# Power_Supply.net
KiCad netlist of a schematic drawn in Altium Designer
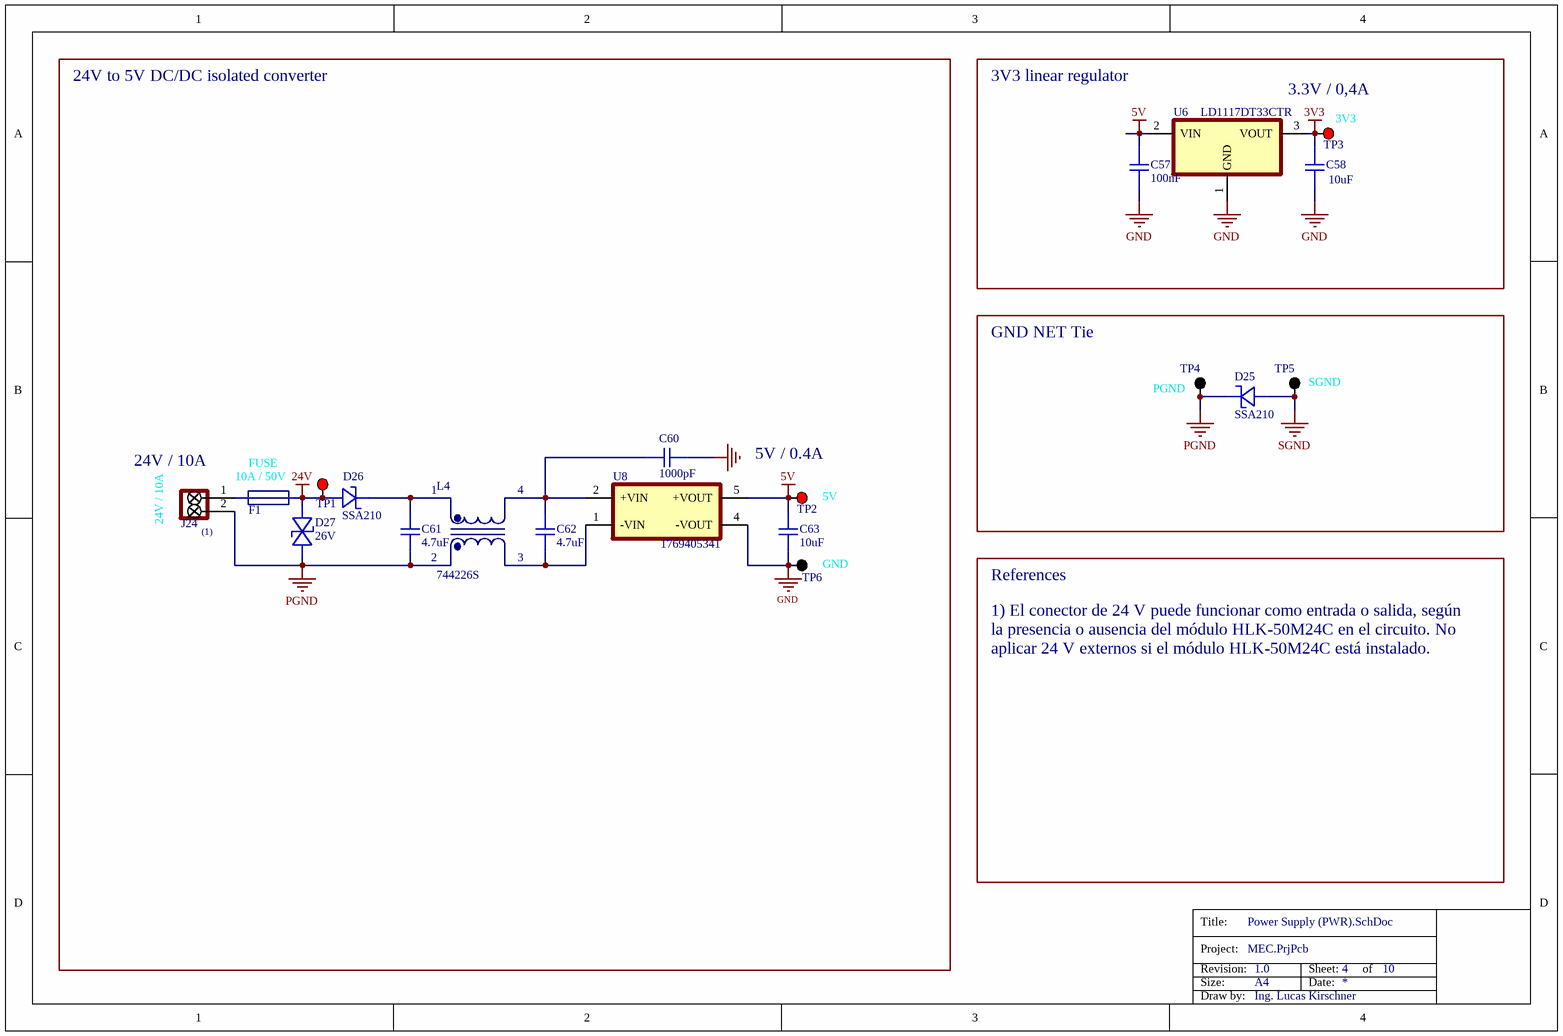
[diagram p0: Power Supply (PWR).SchDoc]

(export (version "E")
  (design (tool "Eeschema 10.0.6"))
  (components
    (comp (ref "C57")
      (value "100nF")
      (footprint "CAPC1005N")
      (description "Multilayer Ceramic Capacitors MLCC - SMD/SMT 50 V 0.1uF X7R 0402 10%")
      (fields (field (name "PART NUMBER") "CC0402KRX5R9BB104") (field (name "MANUFACTURER") "YAGEO"))
      (libsource (lib "SchLib") (part "C-MLCC-100nF-50V-10%-0402"))
    )
    (comp (ref "C58")
      (value "10uF")
      (footprint "CAPC2012N")
      (description "Multilayer Ceramic Capacitors MLCC - SMD/SMT 16V 10uF X5R 0805 10%")
      (fields (field (name "PART NUMBER") "CC0805KKX5R7BB106") (field (name "MANUFACTURER") "YAGEO"))
      (libsource (lib "SchLib") (part "C-MLCC-10uF-16V-10%-0805"))
    )
    (comp (ref "C60")
      (value "1000pF")
      (footprint "CAPC3216N")
      (description "Multilayer Ceramic Capacitors MLCC - SMD/SMT 2kV 1000pF X7R 1206 10%")
      (fields (field (name "PART NUMBER") "CC1206KKX7RDBB102") (field (name "MANUFACTURER") "YAGEO"))
      (libsource (lib "SchLib") (part "C-MLCC-1000pF-2kV-10%-1206"))
    )
    (comp (ref "C61")
      (value "4.7uF")
      (footprint "CAPC2012N")
      (description "Multilayer Ceramic Capacitors MLCC - SMD/SMT 50V 4.7uF X5R 0805 10%")
      (fields (field (name "PART NUMBER") "CC0805KKX5R9BB475") (field (name "MANUFACTURER") "YAGEO"))
      (libsource (lib "SchLib") (part "C-MLCC-4.7uF-50V-10%-0805"))
    )
    (comp (ref "C62")
      (value "4.7uF")
      (footprint "CAPC2012N")
      (description "Multilayer Ceramic Capacitors MLCC - SMD/SMT 50V 4.7uF X5R 0805 10%")
      (fields (field (name "PART NUMBER") "CC0805KKX5R9BB475") (field (name "MANUFACTURER") "YAGEO"))
      (libsource (lib "SchLib") (part "C-MLCC-4.7uF-50V-10%-0805"))
    )
    (comp (ref "C63")
      (value "10uF")
      (footprint "CAPC2012N")
      (description "Multilayer Ceramic Capacitors MLCC - SMD/SMT 16V 10uF X5R 0805 10%")
      (fields (field (name "PART NUMBER") "CC0805KKX5R7BB106") (field (name "MANUFACTURER") "YAGEO"))
      (libsource (lib "SchLib") (part "C-MLCC-10uF-16V-10%-0805"))
    )
    (comp (ref "D25")
      (value "Schottky Diodes")
      (footprint "DIOM5026X229N")
      (description "Schottky Diodes & Rectifiers 2A 100V SMA")
      (fields
        (field (name "MANUFACTURER") "onsemi")
        (field (name "MOUSER PART #") "512-SSA210")
        (field (name "PART NUMBER") "SSA210")
      )
      (libsource (lib "SchLib") (part "D-SCH-2A-100V-SMA"))
    )
    (comp (ref "D26")
      (value "Schottky Diodes")
      (footprint "DIOM5026X229N")
      (description "Schottky Diodes & Rectifiers 2A 100V SMA")
      (fields
        (field (name "MANUFACTURER") "onsemi")
        (field (name "MOUSER PART #") "512-SSA210")
        (field (name "PART NUMBER") "SSA210")
      )
      (libsource (lib "SchLib") (part "D-SCH-2A-100V-SMA"))
    )
    (comp (ref "D27")
      (value "26V")
      (footprint "DIOM5026X229N_NP")
      (description "ESD Protection Diodes / TVS Diodes 400W 26V 5% Bi-Directional")
      (fields (field (name "PART NUMBER") "SMAJ26CA") (field (name "MANUFACTURER") "Littelfuse"))
      (libsource (lib "SchLib") (part "D-TVS-400W-26V-SMA-BI"))
    )
    (comp (ref "F1")
      (value "Cartridge Fuse")
      (footprint "RESC3216N")
      (description "Surface Mount Fuses 1206 high-current met-foil. 10A")
      (fields (field (name "MANUFACTURER") "Bourns") (field (name "MOUSER PART #") "652-SF-1206HH1000R-2"))
      (libsource (lib "SchLib") (part "F-1206-10A-50V-SMT"))
    )
    (comp (ref "J24")
      (value "Terminal Blocks")
      (footprint "CONB_FIX508P-2N")
      (description "Pluggable Terminal Blocks 2 Pos 5.08mm pitch Through Hole Header")
      (fields (field (name "MOUSER PART #") "737-EBA-02-D-BU-01") (field (name "MANUFACTURER") "Adam Tech"))
      (libsource (lib "SchLib") (part "J-02-5P08-TERM-F-VERT-TH"))
    )
    (comp (ref "L4")
      (value "Common Mode Chokes")
      (footprint "INDC6X9.2-4N")
      (description "Common Mode Chokes / Filters WE-SL2 SMD Sectional 2x10uH 1600mA")
      (fields
        (field (name "MANUFACTURER") "Wurth Elektronik")
        (field (name "MOUSER PART #") "710-744226S")
        (field (name "PART NUMBER") "744226S")
      )
      (libsource (lib "SchLib") (part "L-CMC-10uH-1.6A-TH"))
    )
    (comp (ref "TP1")
      (value "Test point")
      (footprint "TP-1MM")
      (description "Test point, 1mm, exposed pad")
      (fields (field (name "JLCPCB PART #") "C5199810"))
      (libsource (lib "SchLib") (part "TP-1MM-SMD"))
    )
    (comp (ref "TP2")
      (value "Test point")
      (footprint "TP-1MM")
      (description "Test point, 1mm, exposed pad")
      (fields (field (name "JLCPCB PART #") "C5199810"))
      (libsource (lib "SchLib") (part "TP-1MM-SMD"))
    )
    (comp (ref "TP3")
      (value "Test point")
      (footprint "TP-1MM")
      (description "Test point, 1mm, exposed pad")
      (fields (field (name "JLCPCB PART #") "C5199810"))
      (libsource (lib "SchLib") (part "TP-1MM-SMD"))
    )
    (comp (ref "TP4")
      (value "Test point")
      (footprint "TPH1.6D3.2BLK")
      (description "Test point black, Mtg Hole 1.6, loop 3.2mm")
      (fields (field (name "PART NUMBER") "5006") (field (name "MANUFACTURER") "Keystone Electronics"))
      (libsource (lib "SchLib") (part "TP-LOOP-D3.2-P1.60-BLK-TH"))
    )
    (comp (ref "TP5")
      (value "Test point")
      (footprint "TPH1.6D3.2BLK")
      (description "Test point black, Mtg Hole 1.6, loop 3.2mm")
      (fields (field (name "PART NUMBER") "5006") (field (name "MANUFACTURER") "Keystone Electronics"))
      (libsource (lib "SchLib") (part "TP-LOOP-D3.2-P1.60-BLK-TH"))
    )
    (comp (ref "TP6")
      (value "Test point")
      (footprint "TPH1.6D3.2BLK")
      (description "Test point black, Mtg Hole 1.6, loop 3.2mm")
      (fields (field (name "PART NUMBER") "5006") (field (name "MANUFACTURER") "Keystone Electronics"))
      (libsource (lib "SchLib") (part "TP-LOOP-D3.2-P1.60-BLK-TH"))
    )
    (comp (ref "U6")
      (value "LDO Voltage Regulators")
      (footprint "TO252P170-3N")
      (description "LDO Voltage Regulators 3.3V 0.8A Positive")
      (fields
        (field (name "MANUFACTURER") "STMicroelectronics")
        (field (name "MOUSER PART #") "511-LD1117DT33C-TR")
        (field (name "PART NUMBER") "LD1117DT33CTR")
      )
      (libsource (lib "SchLib") (part "U-LD1117DT33CTR"))
    )
    (comp (ref "U8")
      (value "Isolated DC/DC Converter")
      (footprint "PKG10.8X12.8-5N")
      (description "Isolated DC/DC Converters - SMD WPME-FISM SMT-8 Modu 24Vin 5Vout 2W 3kV")
      (fields
        (field (name "MANUFACTURER") "Wurth Elektronik")
        (field (name "MOUSER PART #") "710-1769405341")
        (field (name "PART NUMBER") "1769405341")
      )
      (libsource (lib "SchLib") (part "U-1769405341-SMD"))
    )
  )
  (nets
    (net (code "1") (name "3V3") (class "Default")
      (node (ref "C58") (pin "1") (pinfunction "1_1") (pintype "passive"))
      (node (ref "TP3") (pin "1") (pinfunction "1_1") (pintype "passive"))
      (node (ref "U6") (pin "3") (pinfunction "VOUT_3") (pintype "passive"))
    )
    (net (code "2") (name "5V") (class "Default")
      (node (ref "C57") (pin "1") (pinfunction "1_1") (pintype "passive"))
      (node (ref "C63") (pin "1") (pinfunction "1_1") (pintype "passive"))
      (node (ref "TP2") (pin "1") (pinfunction "1_1") (pintype "passive"))
      (node (ref "U6") (pin "2") (pinfunction "VIN_2") (pintype "passive"))
      (node (ref "U8") (pin "5") (pinfunction "+VOUT_5") (pintype "passive"))
    )
    (net (code "3") (name "24V") (class "Default")
      (node (ref "D26") (pin "A") (pinfunction "A_A") (pintype "passive"))
      (node (ref "D27") (pin "2") (pinfunction "2_2") (pintype "passive"))
      (node (ref "F1") (pin "2") (pinfunction "2_2") (pintype "passive"))
      (node (ref "TP1") (pin "1") (pinfunction "1_1") (pintype "passive"))
    )
    (net (code "4") (name "GND") (class "Default")
      (node (ref "C57") (pin "2") (pinfunction "2_2") (pintype "passive"))
      (node (ref "C58") (pin "2") (pinfunction "2_2") (pintype "passive"))
      (node (ref "C60") (pin "2") (pinfunction "2_2") (pintype "passive"))
      (node (ref "C63") (pin "2") (pinfunction "2_2") (pintype "passive"))
      (node (ref "TP6") (pin "1") (pinfunction "1_1") (pintype "passive"))
      (node (ref "U6") (pin "1") (pinfunction "GND_1") (pintype "passive"))
      (node (ref "U8") (pin "4") (pinfunction "-VOUT_4") (pintype "passive"))
    )
    (net (code "5") (name "Net-(C61-Pad1)") (class "Default")
      (node (ref "C61") (pin "1") (pinfunction "1_1") (pintype "passive"))
      (node (ref "D26") (pin "C") (pinfunction "C_C") (pintype "passive"))
      (node (ref "L4") (pin "1") (pinfunction "1_1") (pintype "passive"))
    )
    (net (code "6") (name "Net-(F1-Pad1)") (class "Default")
      (node (ref "F1") (pin "1") (pinfunction "1_1") (pintype "passive"))
      (node (ref "J24") (pin "1") (pinfunction "1_1") (pintype "passive"))
    )
    (net (code "7") (name "Net-(U8-+VIN)") (class "Default")
      (node (ref "C60") (pin "1") (pinfunction "1_1") (pintype "passive"))
      (node (ref "C62") (pin "1") (pinfunction "1_1") (pintype "passive"))
      (node (ref "L4") (pin "4") (pinfunction "4_4") (pintype "passive"))
      (node (ref "U8") (pin "2") (pinfunction "+VIN_2") (pintype "passive"))
    )
    (net (code "8") (name "Net-(U8--VIN)") (class "Default")
      (node (ref "C62") (pin "2") (pinfunction "2_2") (pintype "passive"))
      (node (ref "L4") (pin "3") (pinfunction "3_3") (pintype "passive"))
      (node (ref "U8") (pin "1") (pinfunction "-VIN_1") (pintype "passive"))
    )
    (net (code "9") (name "PGND") (class "Default")
      (node (ref "C61") (pin "2") (pinfunction "2_2") (pintype "passive"))
      (node (ref "D25") (pin "C") (pinfunction "C_C") (pintype "passive"))
      (node (ref "D27") (pin "1") (pinfunction "1_1") (pintype "passive"))
      (node (ref "J24") (pin "2") (pinfunction "2_2") (pintype "passive"))
      (node (ref "L4") (pin "2") (pinfunction "2_2") (pintype "passive"))
      (node (ref "TP4") (pin "1") (pinfunction "1_1") (pintype "passive"))
    )
    (net (code "10") (name "SGND") (class "Default")
      (node (ref "D25") (pin "A") (pinfunction "A_A") (pintype "passive"))
      (node (ref "TP5") (pin "1") (pinfunction "1_1") (pintype "passive"))
    )
  )
)
